# ledcontrol.net
KiCad netlist of a schematic drawn in EAGLE
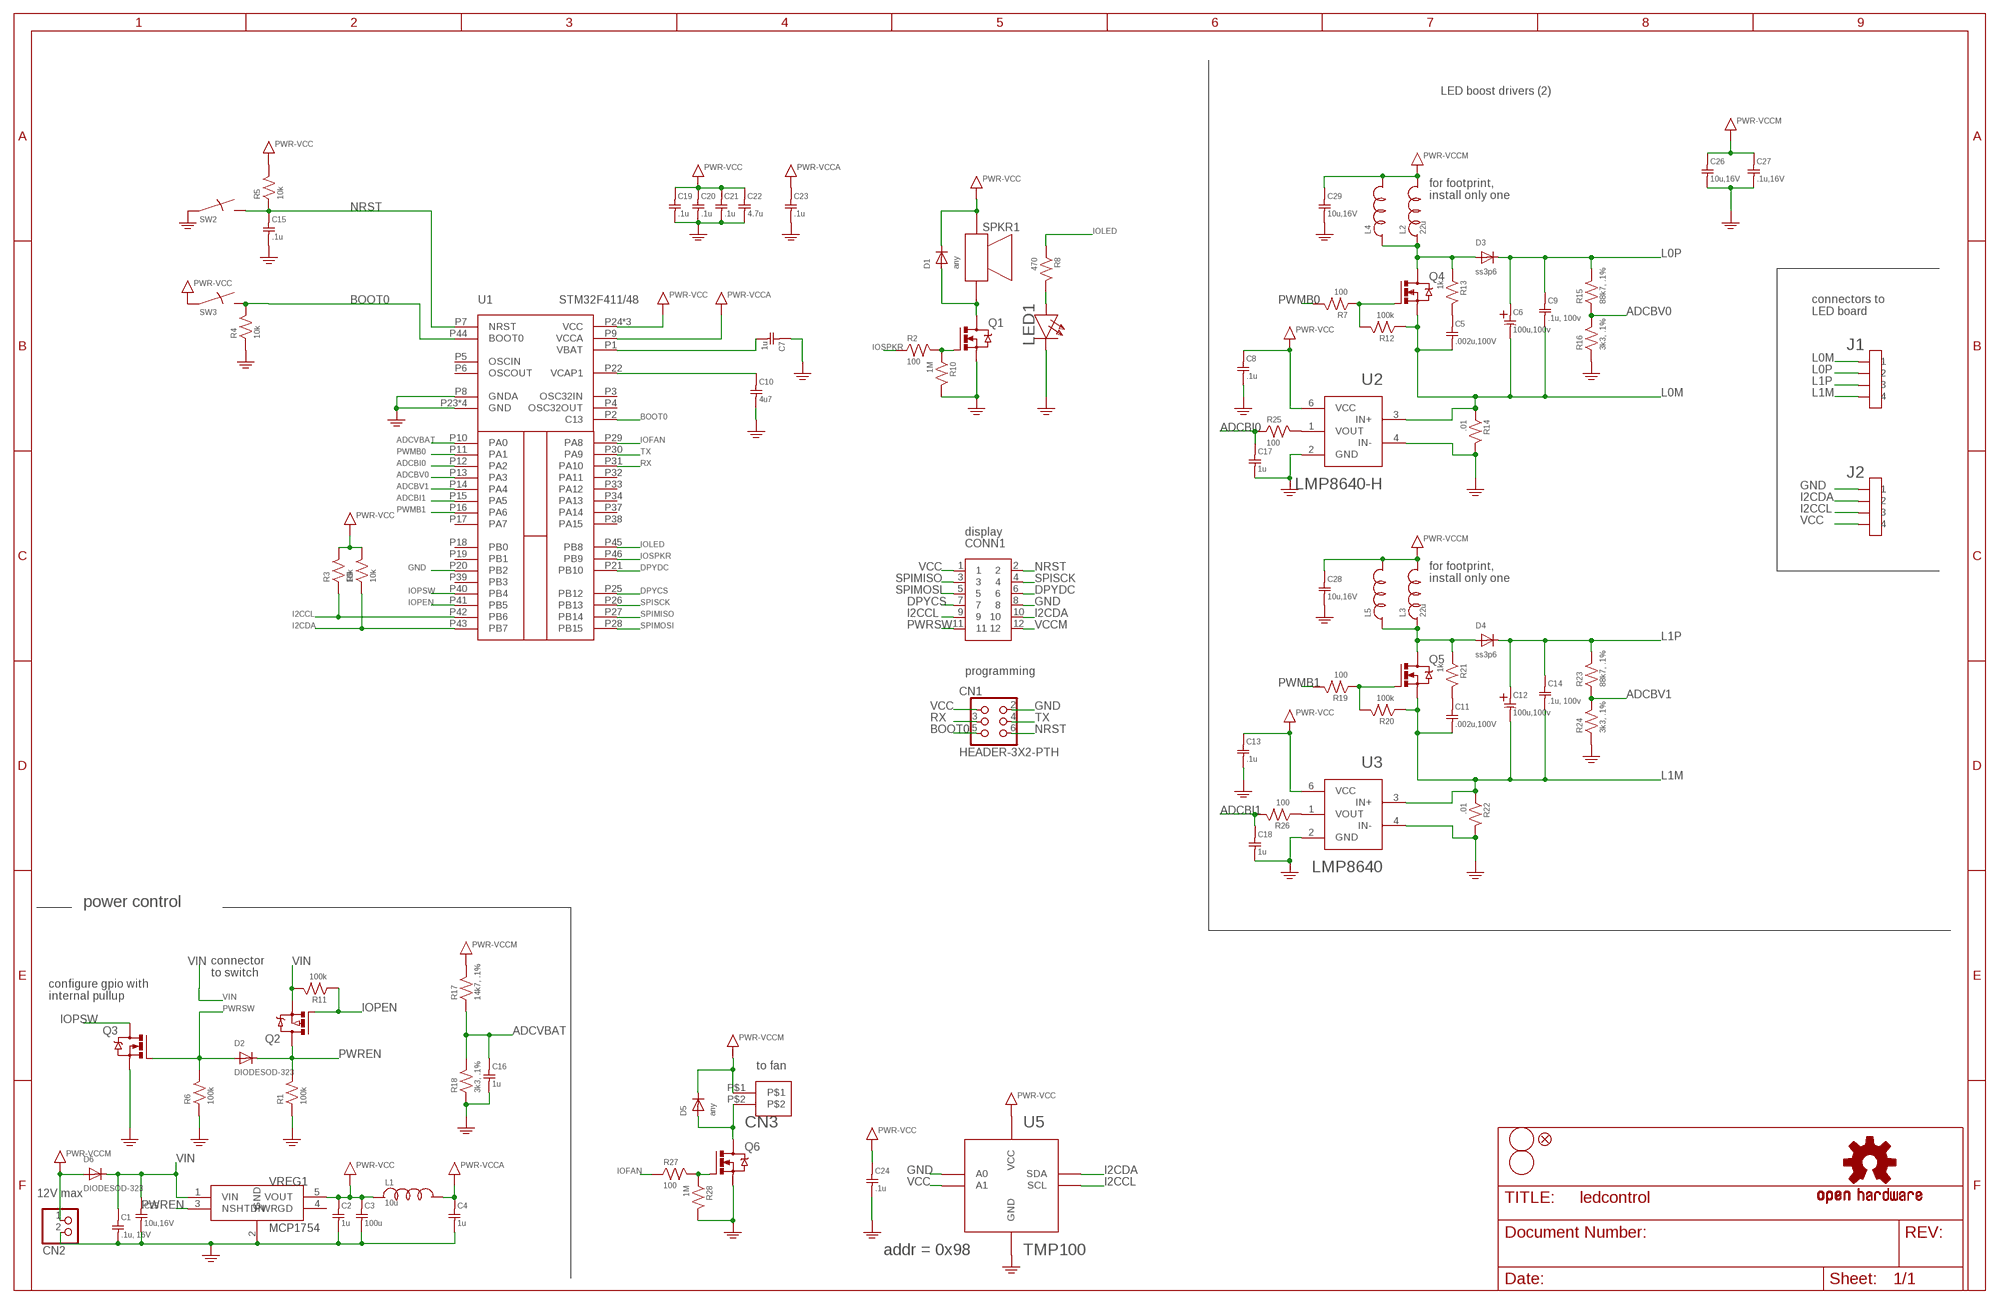
[diagram p0: schematic, sheet 1]

(export (version "E")
  (design (tool "Eeschema 10.0.6"))
  (components
    (comp (ref "C1")
      (value ".1u, 16V")
      (footprint "eagle-import:SMD0603")
      (libsource (lib "eagle-import") (part "C0603"))
    )
    (comp (ref "C2")
      (value "1u")
      (footprint "eagle-import:SMD0603")
      (libsource (lib "eagle-import") (part "C0603"))
    )
    (comp (ref "C3")
      (value "100u")
      (footprint "eagle-import:SMD1210")
      (libsource (lib "eagle-import") (part "C1210"))
    )
    (comp (ref "C4")
      (value "1u")
      (footprint "eagle-import:SMD0603")
      (libsource (lib "eagle-import") (part "C0603"))
    )
    (comp (ref "C5")
      (value ".002u,100V")
      (footprint "eagle-import:SMD0603")
      (libsource (lib "eagle-import") (part "C0603"))
    )
    (comp (ref "C6")
      (value "100u,100v")
      (footprint "eagle-import:CAPKE0")
      (libsource (lib "eagle-import") (part "C-POL-KE0"))
    )
    (comp (ref "C7")
      (value "1u")
      (footprint "eagle-import:SMD0603")
      (libsource (lib "eagle-import") (part "C0603"))
    )
    (comp (ref "C8")
      (value ".1u")
      (footprint "eagle-import:SMD0603")
      (libsource (lib "eagle-import") (part "C0603"))
    )
    (comp (ref "C9")
      (value ".1u, 100v")
      (footprint "eagle-import:SMD0805")
      (libsource (lib "eagle-import") (part "C0805"))
    )
    (comp (ref "C10")
      (value "4u7")
      (footprint "eagle-import:SMD0603")
      (libsource (lib "eagle-import") (part "C0603"))
    )
    (comp (ref "C11")
      (value ".002u,100V")
      (footprint "eagle-import:SMD0603")
      (libsource (lib "eagle-import") (part "C0603"))
    )
    (comp (ref "C12")
      (value "100u,100v")
      (footprint "eagle-import:CAPKE0")
      (libsource (lib "eagle-import") (part "C-POL-KE0"))
    )
    (comp (ref "C13")
      (value ".1u")
      (footprint "eagle-import:SMD0603")
      (libsource (lib "eagle-import") (part "C0603"))
    )
    (comp (ref "C14")
      (value ".1u, 100v")
      (footprint "eagle-import:SMD0805")
      (libsource (lib "eagle-import") (part "C0805"))
    )
    (comp (ref "C15")
      (value ".1u")
      (footprint "eagle-import:SMD0603")
      (libsource (lib "eagle-import") (part "C0603"))
    )
    (comp (ref "C16")
      (value "1u")
      (footprint "eagle-import:SMD0603")
      (libsource (lib "eagle-import") (part "C0603"))
    )
    (comp (ref "C17")
      (value "1u")
      (footprint "eagle-import:SMD0603")
      (libsource (lib "eagle-import") (part "C0603"))
    )
    (comp (ref "C18")
      (value "1u")
      (footprint "eagle-import:SMD0603")
      (libsource (lib "eagle-import") (part "C0603"))
    )
    (comp (ref "C19")
      (value ".1u")
      (footprint "eagle-import:SMD0603")
      (libsource (lib "eagle-import") (part "C0603"))
    )
    (comp (ref "C20")
      (value ".1u")
      (footprint "eagle-import:SMD0603")
      (libsource (lib "eagle-import") (part "C0603"))
    )
    (comp (ref "C21")
      (value ".1u")
      (footprint "eagle-import:SMD0603")
      (libsource (lib "eagle-import") (part "C0603"))
    )
    (comp (ref "C22")
      (value "4.7u")
      (footprint "eagle-import:SMD0603")
      (libsource (lib "eagle-import") (part "C0603"))
    )
    (comp (ref "C23")
      (value ".1u")
      (footprint "eagle-import:SMD0603")
      (libsource (lib "eagle-import") (part "C0603"))
    )
    (comp (ref "C24")
      (value ".1u")
      (footprint "eagle-import:SMD0603")
      (libsource (lib "eagle-import") (part "C0603"))
    )
    (comp (ref "C25")
      (value "10u,16V")
      (footprint "eagle-import:SMD0603")
      (libsource (lib "eagle-import") (part "C0603"))
    )
    (comp (ref "C26")
      (value "10u,16V")
      (footprint "eagle-import:SMD0603")
      (libsource (lib "eagle-import") (part "C0603"))
    )
    (comp (ref "C27")
      (value ".1u,16V")
      (footprint "eagle-import:SMD0603")
      (libsource (lib "eagle-import") (part "C0603"))
    )
    (comp (ref "C28")
      (value "10u,16V")
      (footprint "eagle-import:SMD0603")
      (libsource (lib "eagle-import") (part "C0603"))
    )
    (comp (ref "C29")
      (value "10u,16V")
      (footprint "eagle-import:SMD0603")
      (libsource (lib "eagle-import") (part "C0603"))
    )
    (comp (ref "CN1")
      (value "HEADER-3X2-PTH")
      (footprint "eagle-import:HEADER-3X2-PTH")
      (libsource (lib "eagle-import") (part "HEADER-3X2-PTH"))
    )
    (comp (ref "CN2")
      (value "JST_2PIN-THM-RA")
      (footprint "eagle-import:JST-PH-2-THM-RA")
      (libsource (lib "eagle-import") (part "JST_2PIN-THM-RA"))
    )
    (comp (ref "CN3")
      (value "HEADER-1X2-THM")
      (footprint "eagle-import:HEADER-1X2-THM")
      (libsource (lib "eagle-import") (part "HEADER-1X2-THM"))
    )
    (comp (ref "CONN1")
      (value "HEADER-6X2-PTH")
      (footprint "eagle-import:HEADER-6X2-PTH")
      (libsource (lib "eagle-import") (part "HEADER-6X2-PTH"))
    )
    (comp (ref "D1")
      (value "any")
      (footprint "eagle-import:SOD-323")
      (libsource (lib "eagle-import") (part "DIODESOD-323"))
    )
    (comp (ref "D2")
      (value "DIODESOD-323")
      (footprint "eagle-import:SOD-323")
      (libsource (lib "eagle-import") (part "DIODESOD-323"))
    )
    (comp (ref "D3")
      (value "ss3p6")
      (footprint "eagle-import:DO-214AC")
      (libsource (lib "eagle-import") (part "DIODEDO-214AC"))
    )
    (comp (ref "D4")
      (value "ss3p6")
      (footprint "eagle-import:DO-214AC")
      (libsource (lib "eagle-import") (part "DIODEDO-214AC"))
    )
    (comp (ref "D5")
      (value "any")
      (footprint "eagle-import:SOD-323")
      (libsource (lib "eagle-import") (part "DIODESOD-323"))
    )
    (comp (ref "D6")
      (value "DIODESOD-323")
      (footprint "eagle-import:SOD-323")
      (libsource (lib "eagle-import") (part "DIODESOD-323"))
    )
    (comp (ref "FID1")
      (value "FIDUCIALUFIDUCIAL")
      (footprint "eagle-import:MICRO-FIDUCIAL")
      (libsource (lib "eagle-import") (part "FIDUCIALUFIDUCIAL"))
    )
    (comp (ref "J1")
      (value "HEADER-4X1-PTH")
      (footprint "eagle-import:HEADER-4X1-PTH")
      (libsource (lib "eagle-import") (part "HEADER-4X1-PTH"))
    )
    (comp (ref "J2")
      (value "HEADER-4X1-PTH")
      (footprint "eagle-import:HEADER-4X1-PTH")
      (libsource (lib "eagle-import") (part "HEADER-4X1-PTH"))
    )
    (comp (ref "L1")
      (value "10u")
      (footprint "eagle-import:SMD0603")
      (libsource (lib "eagle-import") (part "LSMD0603"))
    )
    (comp (ref "L2")
      (value "22u")
      (footprint "eagle-import:BOURNS2303")
      (libsource (lib "eagle-import") (part "L2303"))
    )
    (comp (ref "L3")
      (value "22u")
      (footprint "eagle-import:BOURNS2303")
      (libsource (lib "eagle-import") (part "L2303"))
    )
    (comp (ref "L4")
      (value "L-SRR1260")
      (footprint "eagle-import:SRR1260")
      (libsource (lib "eagle-import") (part "L-SRR1260"))
    )
    (comp (ref "L5")
      (value "L-SRR1260")
      (footprint "eagle-import:SRR1260")
      (libsource (lib "eagle-import") (part "L-SRR1260"))
    )
    (comp (ref "LED1")
      (value "white")
      (footprint "eagle-import:SMD0603D")
      (libsource (lib "eagle-import") (part "LED"))
    )
    (comp (ref "LOGO1")
      (value "OSHW-LOGOS")
      (footprint "eagle-import:OSHW-LOGO-S")
      (libsource (lib "eagle-import") (part "OSHW-LOGOS"))
    )
    (comp (ref "Q1")
      (value "IRLML6344TRPBF")
      (footprint "eagle-import:SOT-23-3")
      (libsource (lib "eagle-import") (part "MOSFETSOT-23"))
    )
    (comp (ref "Q2")
      (value "MOSFET-P")
      (footprint "eagle-import:SOT-23-3@1")
      (libsource (lib "eagle-import") (part "MOSFET-P"))
    )
    (comp (ref "Q3")
      (value "MOSFETSOT-23")
      (footprint "eagle-import:SOT-23-3")
      (libsource (lib "eagle-import") (part "MOSFETSOT-23"))
    )
    (comp (ref "Q4")
      (value "AON6246")
      (footprint "eagle-import:DFN5X6-8LEP1")
      (libsource (lib "eagle-import") (part "MOSFET-DFN5X6"))
    )
    (comp (ref "Q5")
      (value "AON6246")
      (footprint "eagle-import:DFN5X6-8LEP1")
      (libsource (lib "eagle-import") (part "MOSFET-DFN5X6"))
    )
    (comp (ref "Q6")
      (value "IRLML6344TRPBF")
      (footprint "eagle-import:SOT-23-3")
      (libsource (lib "eagle-import") (part "MOSFETSOT-23"))
    )
    (comp (ref "R1")
      (value "100k")
      (footprint "eagle-import:SMD0603")
      (libsource (lib "eagle-import") (part "R0603"))
    )
    (comp (ref "R2")
      (value "100")
      (footprint "eagle-import:SMD0603")
      (libsource (lib "eagle-import") (part "R0603"))
    )
    (comp (ref "R3")
      (value "10k")
      (footprint "eagle-import:SMD0603")
      (libsource (lib "eagle-import") (part "R0603"))
    )
    (comp (ref "R4")
      (value "10k")
      (footprint "eagle-import:SMD0603")
      (libsource (lib "eagle-import") (part "R0603"))
    )
    (comp (ref "R5")
      (value "10k")
      (footprint "eagle-import:SMD0603")
      (libsource (lib "eagle-import") (part "R0603"))
    )
    (comp (ref "R6")
      (value "100k")
      (footprint "eagle-import:SMD0603")
      (libsource (lib "eagle-import") (part "R0603"))
    )
    (comp (ref "R7")
      (value "100")
      (footprint "eagle-import:SMD0603")
      (libsource (lib "eagle-import") (part "R0603"))
    )
    (comp (ref "R8")
      (value "470")
      (footprint "eagle-import:SMD0603")
      (libsource (lib "eagle-import") (part "R0603"))
    )
    (comp (ref "R9")
      (value "10k")
      (footprint "eagle-import:SMD0603")
      (libsource (lib "eagle-import") (part "R0603"))
    )
    (comp (ref "R10")
      (value "1M")
      (footprint "eagle-import:SMD0603")
      (libsource (lib "eagle-import") (part "R0603"))
    )
    (comp (ref "R11")
      (value "100k")
      (footprint "eagle-import:SMD0603")
      (libsource (lib "eagle-import") (part "R0603"))
    )
    (comp (ref "R12")
      (value "100k")
      (footprint "eagle-import:SMD0603")
      (libsource (lib "eagle-import") (part "R0603"))
    )
    (comp (ref "R13")
      (value "1k")
      (footprint "eagle-import:SMD0603")
      (libsource (lib "eagle-import") (part "R0603"))
    )
    (comp (ref "R14")
      (value ".01")
      (footprint "eagle-import:SMD1206")
      (libsource (lib "eagle-import") (part "R1206"))
    )
    (comp (ref "R15")
      (value "88k7, .1%")
      (footprint "eagle-import:SMD0603")
      (libsource (lib "eagle-import") (part "R0603"))
    )
    (comp (ref "R16")
      (value "3k3, .1%")
      (footprint "eagle-import:SMD0603")
      (libsource (lib "eagle-import") (part "R0603"))
    )
    (comp (ref "R17")
      (value "14k7, .1%")
      (footprint "eagle-import:SMD0603")
      (libsource (lib "eagle-import") (part "R0603"))
    )
    (comp (ref "R18")
      (value "3k3, .1%")
      (footprint "eagle-import:SMD0603")
      (libsource (lib "eagle-import") (part "R0603"))
    )
    (comp (ref "R19")
      (value "100")
      (footprint "eagle-import:SMD0603")
      (libsource (lib "eagle-import") (part "R0603"))
    )
    (comp (ref "R20")
      (value "100k")
      (footprint "eagle-import:SMD0603")
      (libsource (lib "eagle-import") (part "R0603"))
    )
    (comp (ref "R21")
      (value "1k")
      (footprint "eagle-import:SMD0603")
      (libsource (lib "eagle-import") (part "R0603"))
    )
    (comp (ref "R22")
      (value ".01")
      (footprint "eagle-import:SMD1206")
      (libsource (lib "eagle-import") (part "R1206"))
    )
    (comp (ref "R23")
      (value "88k7, .1%")
      (footprint "eagle-import:SMD0603")
      (libsource (lib "eagle-import") (part "R0603"))
    )
    (comp (ref "R24")
      (value "3k3, .1%")
      (footprint "eagle-import:SMD0603")
      (libsource (lib "eagle-import") (part "R0603"))
    )
    (comp (ref "R25")
      (value "100")
      (footprint "eagle-import:SMD0603")
      (libsource (lib "eagle-import") (part "R0603"))
    )
    (comp (ref "R26")
      (value "100")
      (footprint "eagle-import:SMD0603")
      (libsource (lib "eagle-import") (part "R0603"))
    )
    (comp (ref "R27")
      (value "100")
      (footprint "eagle-import:SMD0603")
      (libsource (lib "eagle-import") (part "R0603"))
    )
    (comp (ref "R28")
      (value "1M")
      (footprint "eagle-import:SMD0603")
      (libsource (lib "eagle-import") (part "R0603"))
    )
    (comp (ref "SPKR1")
      (value "PUI-5040")
      (footprint "eagle-import:PUI-0540")
      (libsource (lib "eagle-import") (part "PUI-5040"))
    )
    (comp (ref "SW2")
      (value "SWITCHKMR211")
      (footprint "eagle-import:KMR211")
      (libsource (lib "eagle-import") (part "SWITCHKMR211"))
    )
    (comp (ref "SW3")
      (value "SWITCHKMR211")
      (footprint "eagle-import:KMR211")
      (libsource (lib "eagle-import") (part "SWITCHKMR211"))
    )
    (comp (ref "U$1")
      (value "FIDUCIAL")
      (footprint "eagle-import:FIDUCIAL_1MM")
      (libsource (lib "eagle-import") (part "FIDUCIAL"))
    )
    (comp (ref "U$2")
      (value "FIDUCIAL")
      (footprint "eagle-import:FIDUCIAL_1MM")
      (libsource (lib "eagle-import") (part "FIDUCIAL"))
    )
    (comp (ref "U1")
      (value "STM32F411/48")
      (footprint "eagle-import:UQPFN48")
      (libsource (lib "eagle-import") (part "STM32F411/48"))
    )
    (comp (ref "U2")
      (value "LMP8640-H")
      (footprint "eagle-import:SOT-23-6")
      (libsource (lib "eagle-import") (part "LMP8640"))
    )
    (comp (ref "U3")
      (value "LMP8640")
      (footprint "eagle-import:SOT-23-6")
      (libsource (lib "eagle-import") (part "LMP8640"))
    )
    (comp (ref "U5")
      (value "TMP100")
      (footprint "eagle-import:SOT-23-6")
      (libsource (lib "eagle-import") (part "TMP100"))
    )
    (comp (ref "VREG1")
      (value "MCP1754")
      (footprint "eagle-import:SOT-23-5")
      (libsource (lib "eagle-import") (part "MCP1824"))
    )
  )
  (nets
    (net (code "1") (name "/ADCBI0") (class "Default")
      (node (ref "C17") (pin "1") (pinfunction "P$1_1") (pintype "passive"))
      (node (ref "R25") (pin "1") (pinfunction "P$1_1") (pintype "passive"))
      (node (ref "U1") (pin "P12") (pinfunction "PA2_P12") (pintype "bidirectional"))
    )
    (net (code "2") (name "/ADCBI1") (class "Default")
      (node (ref "C18") (pin "1") (pinfunction "P$1_1") (pintype "passive"))
      (node (ref "R26") (pin "2") (pinfunction "P$2_2") (pintype "passive"))
      (node (ref "U1") (pin "P15") (pinfunction "PA5_P15") (pintype "bidirectional"))
    )
    (net (code "3") (name "/ADCBV0") (class "Default")
      (node (ref "R15") (pin "1") (pinfunction "P$1_1") (pintype "passive"))
      (node (ref "R16") (pin "2") (pinfunction "P$2_2") (pintype "passive"))
      (node (ref "U1") (pin "P13") (pinfunction "PA3_P13") (pintype "bidirectional"))
    )
    (net (code "4") (name "/ADCBV1") (class "Default")
      (node (ref "R23") (pin "1") (pinfunction "P$1_1") (pintype "passive"))
      (node (ref "R24") (pin "2") (pinfunction "P$2_2") (pintype "passive"))
      (node (ref "U1") (pin "P14") (pinfunction "PA4_P14") (pintype "bidirectional"))
    )
    (net (code "5") (name "/ADCVBAT") (class "Default")
      (node (ref "C16") (pin "1") (pinfunction "P$1_1") (pintype "passive"))
      (node (ref "R17") (pin "1") (pinfunction "P$1_1") (pintype "passive"))
      (node (ref "R18") (pin "2") (pinfunction "P$2_2") (pintype "passive"))
      (node (ref "U1") (pin "P10") (pinfunction "PA0_P10") (pintype "bidirectional"))
    )
    (net (code "6") (name "/BOOT0") (class "Default")
      (node (ref "CN1") (pin "5") (pinfunction "P$5_5") (pintype "passive"))
      (node (ref "R4") (pin "2") (pinfunction "P$2_2") (pintype "passive"))
      (node (ref "SW3") (pin "2") (pinfunction "P$2_2") (pintype "passive"))
      (node (ref "SW3") (pin "4") (pinfunction "P$2_4") (pintype "passive"))
      (node (ref "U1") (pin "P2") (pinfunction "C13_P2") (pintype "bidirectional"))
      (node (ref "U1") (pin "P44") (pinfunction "BOOT0_P44") (pintype "bidirectional"))
    )
    (net (code "7") (name "/DPYCS") (class "Default")
      (node (ref "CONN1") (pin "7") (pinfunction "7_7") (pintype "bidirectional"))
      (node (ref "U1") (pin "P25") (pinfunction "PB12_P25") (pintype "bidirectional"))
    )
    (net (code "8") (name "/DPYDC") (class "Default")
      (node (ref "CONN1") (pin "6") (pinfunction "6_6") (pintype "bidirectional"))
      (node (ref "U1") (pin "P21") (pinfunction "PB10_P21") (pintype "bidirectional"))
    )
    (net (code "9") (name "/I2CCL") (class "Default")
      (node (ref "CONN1") (pin "9") (pinfunction "9_9") (pintype "bidirectional"))
      (node (ref "J2") (pin "P$3") (pinfunction "3_P$3") (pintype "bidirectional"))
      (node (ref "R3") (pin "1") (pinfunction "P$1_1") (pintype "passive"))
      (node (ref "U1") (pin "P42") (pinfunction "PB6_P42") (pintype "bidirectional"))
      (node (ref "U5") (pin "1") (pinfunction "SCL_1") (pintype "bidirectional"))
    )
    (net (code "10") (name "/I2CDA") (class "Default")
      (node (ref "CONN1") (pin "10") (pinfunction "10_10") (pintype "bidirectional"))
      (node (ref "J2") (pin "P$2") (pinfunction "2_P$2") (pintype "bidirectional"))
      (node (ref "R9") (pin "1") (pinfunction "P$1_1") (pintype "passive"))
      (node (ref "U1") (pin "P43") (pinfunction "PB7_P43") (pintype "bidirectional"))
      (node (ref "U5") (pin "6") (pinfunction "SDA_6") (pintype "bidirectional"))
    )
    (net (code "11") (name "/IOFAN") (class "Default")
      (node (ref "R27") (pin "1") (pinfunction "P$1_1") (pintype "passive"))
      (node (ref "U1") (pin "P29") (pinfunction "PA8_P29") (pintype "bidirectional"))
    )
    (net (code "12") (name "/IOLED") (class "Default")
      (node (ref "R8") (pin "1") (pinfunction "P$1_1") (pintype "passive"))
      (node (ref "U1") (pin "P45") (pinfunction "PB8_P45") (pintype "bidirectional"))
    )
    (net (code "13") (name "/IOPEN") (class "Default")
      (node (ref "Q2") (pin "1") (pinfunction "G_1") (pintype "passive"))
      (node (ref "R11") (pin "1") (pinfunction "P$1_1") (pintype "passive"))
      (node (ref "U1") (pin "P41") (pinfunction "PB5_P41") (pintype "bidirectional"))
    )
    (net (code "14") (name "/IOPSW") (class "Default")
      (node (ref "Q3") (pin "3") (pinfunction "D_3") (pintype "passive"))
      (node (ref "U1") (pin "P40") (pinfunction "PB4_P40") (pintype "bidirectional"))
    )
    (net (code "15") (name "/IOSPKR") (class "Default")
      (node (ref "R2") (pin "1") (pinfunction "P$1_1") (pintype "passive"))
      (node (ref "U1") (pin "P46") (pinfunction "PB9_P46") (pintype "bidirectional"))
    )
    (net (code "16") (name "/L0M") (class "Default")
      (node (ref "C5") (pin "2") (pinfunction "P$2_2") (pintype "passive"))
      (node (ref "C6") (pin "N") (pinfunction "P$2_N") (pintype "passive"))
      (node (ref "C9") (pin "2") (pinfunction "P$2_2") (pintype "passive"))
      (node (ref "J1") (pin "P$1") (pinfunction "1_P$1") (pintype "bidirectional"))
      (node (ref "Q4") (pin "P$1") (pinfunction "S_P$1") (pintype "passive"))
      (node (ref "Q4") (pin "P$2") (pinfunction "S_P$2") (pintype "passive"))
      (node (ref "Q4") (pin "P$3") (pinfunction "S_P$3") (pintype "passive"))
      (node (ref "R12") (pin "1") (pinfunction "P$1_1") (pintype "passive"))
      (node (ref "R14") (pin "1") (pinfunction "P$1_1") (pintype "passive"))
      (node (ref "U2") (pin "3") (pinfunction "IN+_3") (pintype "bidirectional"))
    )
    (net (code "17") (name "/L0P") (class "Default")
      (node (ref "C6") (pin "P") (pinfunction "P$1_P") (pintype "passive"))
      (node (ref "C9") (pin "1") (pinfunction "P$1_1") (pintype "passive"))
      (node (ref "D3") (pin "C") (pinfunction "C_C") (pintype "passive"))
      (node (ref "J1") (pin "P$2") (pinfunction "2_P$2") (pintype "bidirectional"))
      (node (ref "R15") (pin "2") (pinfunction "P$2_2") (pintype "passive"))
    )
    (net (code "18") (name "/L1M") (class "Default")
      (node (ref "C11") (pin "2") (pinfunction "P$2_2") (pintype "passive"))
      (node (ref "C12") (pin "N") (pinfunction "P$2_N") (pintype "passive"))
      (node (ref "C14") (pin "2") (pinfunction "P$2_2") (pintype "passive"))
      (node (ref "J1") (pin "P$4") (pinfunction "4_P$4") (pintype "bidirectional"))
      (node (ref "Q5") (pin "P$1") (pinfunction "S_P$1") (pintype "passive"))
      (node (ref "Q5") (pin "P$2") (pinfunction "S_P$2") (pintype "passive"))
      (node (ref "Q5") (pin "P$3") (pinfunction "S_P$3") (pintype "passive"))
      (node (ref "R20") (pin "1") (pinfunction "P$1_1") (pintype "passive"))
      (node (ref "R22") (pin "1") (pinfunction "P$1_1") (pintype "passive"))
      (node (ref "U3") (pin "3") (pinfunction "IN+_3") (pintype "bidirectional"))
    )
    (net (code "19") (name "/L1P") (class "Default")
      (node (ref "C12") (pin "P") (pinfunction "P$1_P") (pintype "passive"))
      (node (ref "C14") (pin "1") (pinfunction "P$1_1") (pintype "passive"))
      (node (ref "D4") (pin "C") (pinfunction "C_C") (pintype "passive"))
      (node (ref "J1") (pin "P$3") (pinfunction "3_P$3") (pintype "bidirectional"))
      (node (ref "R23") (pin "2") (pinfunction "P$2_2") (pintype "passive"))
    )
    (net (code "20") (name "/NRST") (class "Default")
      (node (ref "C15") (pin "1") (pinfunction "P$1_1") (pintype "passive"))
      (node (ref "CN1") (pin "6") (pinfunction "P$6_6") (pintype "passive"))
      (node (ref "CONN1") (pin "2") (pinfunction "2_2") (pintype "bidirectional"))
      (node (ref "R5") (pin "1") (pinfunction "P$1_1") (pintype "passive"))
      (node (ref "SW2") (pin "2") (pinfunction "P$2_2") (pintype "passive"))
      (node (ref "SW2") (pin "4") (pinfunction "P$2_4") (pintype "passive"))
      (node (ref "U1") (pin "P7") (pinfunction "NRST_P7") (pintype "bidirectional"))
    )
    (net (code "21") (name "/PWMB0") (class "Default")
      (node (ref "R7") (pin "2") (pinfunction "P$2_2") (pintype "passive"))
      (node (ref "U1") (pin "P11") (pinfunction "PA1_P11") (pintype "bidirectional"))
    )
    (net (code "22") (name "/PWMB1") (class "Default")
      (node (ref "R19") (pin "2") (pinfunction "P$2_2") (pintype "passive"))
      (node (ref "U1") (pin "P16") (pinfunction "PA6_P16") (pintype "bidirectional"))
    )
    (net (code "23") (name "/PWREN") (class "Default")
      (node (ref "D2") (pin "C") (pinfunction "C_C") (pintype "passive"))
      (node (ref "Q2") (pin "3") (pinfunction "D_3") (pintype "passive"))
      (node (ref "R1") (pin "2") (pinfunction "P$2_2") (pintype "passive"))
      (node (ref "VREG1") (pin "3") (pinfunction "NSHTDN_3") (pintype "bidirectional"))
    )
    (net (code "24") (name "/PWRSW") (class "Default")
      (node (ref "CONN1") (pin "11") (pinfunction "11_11") (pintype "bidirectional"))
      (node (ref "D2") (pin "A") (pinfunction "A_A") (pintype "passive"))
      (node (ref "Q3") (pin "1") (pinfunction "G_1") (pintype "passive"))
      (node (ref "R6") (pin "2") (pinfunction "P$2_2") (pintype "passive"))
    )
    (net (code "25") (name "/RX") (class "Default")
      (node (ref "CN1") (pin "3") (pinfunction "P$3_3") (pintype "passive"))
      (node (ref "U1") (pin "P31") (pinfunction "PA10_P31") (pintype "bidirectional"))
    )
    (net (code "26") (name "/SPIMISO") (class "Default")
      (node (ref "CONN1") (pin "3") (pinfunction "3_3") (pintype "bidirectional"))
      (node (ref "U1") (pin "P27") (pinfunction "PB14_P27") (pintype "bidirectional"))
    )
    (net (code "27") (name "/SPIMOSI") (class "Default")
      (node (ref "CONN1") (pin "5") (pinfunction "5_5") (pintype "bidirectional"))
      (node (ref "U1") (pin "P28") (pinfunction "PB15_P28") (pintype "bidirectional"))
    )
    (net (code "28") (name "/SPISCK") (class "Default")
      (node (ref "CONN1") (pin "4") (pinfunction "4_4") (pintype "bidirectional"))
      (node (ref "U1") (pin "P26") (pinfunction "PB13_P26") (pintype "bidirectional"))
    )
    (net (code "29") (name "/TX") (class "Default")
      (node (ref "CN1") (pin "4") (pinfunction "P$4_4") (pintype "passive"))
      (node (ref "U1") (pin "P30") (pinfunction "PA9_P30") (pintype "bidirectional"))
    )
    (net (code "30") (name "/VIN") (class "Default")
      (node (ref "C1") (pin "1") (pinfunction "P$1_1") (pintype "passive"))
      (node (ref "C25") (pin "1") (pinfunction "P$1_1") (pintype "passive"))
      (node (ref "D6") (pin "C") (pinfunction "C_C") (pintype "passive"))
      (node (ref "Q2") (pin "2") (pinfunction "S_2") (pintype "passive"))
      (node (ref "R11") (pin "2") (pinfunction "P$2_2") (pintype "passive"))
      (node (ref "VREG1") (pin "1") (pinfunction "VIN_1") (pintype "bidirectional"))
    )
    (net (code "31") (name "Net-(C5-P$1)") (class "Default")
      (node (ref "C5") (pin "1") (pinfunction "P$1_1") (pintype "passive"))
      (node (ref "R13") (pin "2") (pinfunction "P$2_2") (pintype "passive"))
    )
    (net (code "32") (name "Net-(C7-P$2)") (class "Default")
      (node (ref "C7") (pin "2") (pinfunction "P$2_2") (pintype "passive"))
      (node (ref "U1") (pin "P1") (pinfunction "VBAT_P1") (pintype "bidirectional"))
    )
    (net (code "33") (name "Net-(C10-P$1)") (class "Default")
      (node (ref "C10") (pin "1") (pinfunction "P$1_1") (pintype "passive"))
      (node (ref "U1") (pin "P22") (pinfunction "VCAP1_P22") (pintype "bidirectional"))
    )
    (net (code "34") (name "Net-(C11-P$1)") (class "Default")
      (node (ref "C11") (pin "1") (pinfunction "P$1_1") (pintype "passive"))
      (node (ref "R21") (pin "2") (pinfunction "P$2_2") (pintype "passive"))
    )
    (net (code "35") (name "Net-(Q1-D)") (class "Default")
      (node (ref "D1") (pin "A") (pinfunction "A_A") (pintype "passive"))
      (node (ref "Q1") (pin "3") (pinfunction "D_3") (pintype "passive"))
      (node (ref "SPKR1") (pin "P2") (pinfunction "P2_P2") (pintype "input"))
    )
    (net (code "36") (name "Net-(Q1-G)") (class "Default")
      (node (ref "Q1") (pin "1") (pinfunction "G_1") (pintype "passive"))
      (node (ref "R10") (pin "1") (pinfunction "P$1_1") (pintype "passive"))
      (node (ref "R2") (pin "2") (pinfunction "P$2_2") (pintype "passive"))
    )
    (net (code "37") (name "Net-(Q4-G)") (class "Default")
      (node (ref "Q4") (pin "P$4") (pinfunction "G_P$4") (pintype "passive"))
      (node (ref "R12") (pin "2") (pinfunction "P$2_2") (pintype "passive"))
      (node (ref "R7") (pin "1") (pinfunction "P$1_1") (pintype "passive"))
    )
    (net (code "38") (name "Net-(Q5-G)") (class "Default")
      (node (ref "Q5") (pin "P$4") (pinfunction "G_P$4") (pintype "passive"))
      (node (ref "R19") (pin "1") (pinfunction "P$1_1") (pintype "passive"))
      (node (ref "R20") (pin "2") (pinfunction "P$2_2") (pintype "passive"))
    )
    (net (code "39") (name "Net-(Q6-D)") (class "Default")
      (node (ref "CN3") (pin "P$2") (pinfunction "P$2_P$2") (pintype "bidirectional"))
      (node (ref "D5") (pin "A") (pinfunction "A_A") (pintype "passive"))
      (node (ref "Q6") (pin "3") (pinfunction "D_3") (pintype "passive"))
    )
    (net (code "40") (name "Net-(Q6-G)") (class "Default")
      (node (ref "Q6") (pin "1") (pinfunction "G_1") (pintype "passive"))
      (node (ref "R27") (pin "2") (pinfunction "P$2_2") (pintype "passive"))
      (node (ref "R28") (pin "1") (pinfunction "P$1_1") (pintype "passive"))
    )
    (net (code "41") (name "Net-(R8-P$2)") (class "Default")
      (node (ref "LED1") (pin "A") (pinfunction "A_A") (pintype "passive"))
      (node (ref "R8") (pin "2") (pinfunction "P$2_2") (pintype "passive"))
    )
    (net (code "42") (name "Net-(R13-P$1)") (class "Default")
      (node (ref "D3") (pin "A") (pinfunction "A_A") (pintype "passive"))
      (node (ref "L2") (pin "P$1") (pinfunction "P$1_P$1") (pintype "passive"))
      (node (ref "L4") (pin "P$1") (pinfunction "P$1_P$1") (pintype "passive"))
      (node (ref "Q4") (pin "P$5") (pinfunction "D_P$5") (pintype "passive"))
      (node (ref "Q4") (pin "P$6") (pinfunction "D_P$6") (pintype "passive"))
      (node (ref "Q4") (pin "P$7") (pinfunction "D_P$7") (pintype "passive"))
      (node (ref "Q4") (pin "P$8") (pinfunction "D_P$8") (pintype "passive"))
      (node (ref "Q4") (pin "P$9") (pinfunction "D_P$9") (pintype "passive"))
      (node (ref "R13") (pin "1") (pinfunction "P$1_1") (pintype "passive"))
    )
    (net (code "43") (name "Net-(R21-P$1)") (class "Default")
      (node (ref "D4") (pin "A") (pinfunction "A_A") (pintype "passive"))
      (node (ref "L3") (pin "P$1") (pinfunction "P$1_P$1") (pintype "passive"))
      (node (ref "L5") (pin "P$1") (pinfunction "P$1_P$1") (pintype "passive"))
      (node (ref "Q5") (pin "P$5") (pinfunction "D_P$5") (pintype "passive"))
      (node (ref "Q5") (pin "P$6") (pinfunction "D_P$6") (pintype "passive"))
      (node (ref "Q5") (pin "P$7") (pinfunction "D_P$7") (pintype "passive"))
      (node (ref "Q5") (pin "P$8") (pinfunction "D_P$8") (pintype "passive"))
      (node (ref "Q5") (pin "P$9") (pinfunction "D_P$9") (pintype "passive"))
      (node (ref "R21") (pin "1") (pinfunction "P$1_1") (pintype "passive"))
    )
    (net (code "44") (name "Net-(R25-P$2)") (class "Default")
      (node (ref "R25") (pin "2") (pinfunction "P$2_2") (pintype "passive"))
      (node (ref "U2") (pin "1") (pinfunction "VOUT_1") (pintype "bidirectional"))
    )
    (net (code "45") (name "Net-(R26-P$1)") (class "Default")
      (node (ref "R26") (pin "1") (pinfunction "P$1_1") (pintype "passive"))
      (node (ref "U3") (pin "1") (pinfunction "VOUT_1") (pintype "bidirectional"))
    )
    (net (code "46") (name "PWR-GND") (class "Default")
      (node (ref "C1") (pin "2") (pinfunction "P$2_2") (pintype "passive"))
      (node (ref "C10") (pin "2") (pinfunction "P$2_2") (pintype "passive"))
      (node (ref "C13") (pin "2") (pinfunction "P$2_2") (pintype "passive"))
      (node (ref "C15") (pin "2") (pinfunction "P$2_2") (pintype "passive"))
      (node (ref "C16") (pin "2") (pinfunction "P$2_2") (pintype "passive"))
      (node (ref "C17") (pin "2") (pinfunction "P$2_2") (pintype "passive"))
      (node (ref "C18") (pin "2") (pinfunction "P$2_2") (pintype "passive"))
      (node (ref "C19") (pin "2") (pinfunction "P$2_2") (pintype "passive"))
      (node (ref "C2") (pin "2") (pinfunction "P$2_2") (pintype "passive"))
      (node (ref "C20") (pin "2") (pinfunction "P$2_2") (pintype "passive"))
      (node (ref "C21") (pin "2") (pinfunction "P$2_2") (pintype "passive"))
      (node (ref "C22") (pin "2") (pinfunction "P$2_2") (pintype "passive"))
      (node (ref "C23") (pin "2") (pinfunction "P$2_2") (pintype "passive"))
      (node (ref "C24") (pin "2") (pinfunction "P$2_2") (pintype "passive"))
      (node (ref "C25") (pin "2") (pinfunction "P$2_2") (pintype "passive"))
      (node (ref "C26") (pin "2") (pinfunction "P$2_2") (pintype "passive"))
      (node (ref "C27") (pin "2") (pinfunction "P$2_2") (pintype "passive"))
      (node (ref "C28") (pin "2") (pinfunction "P$2_2") (pintype "passive"))
      (node (ref "C29") (pin "2") (pinfunction "P$2_2") (pintype "passive"))
      (node (ref "C3") (pin "2") (pinfunction "P$2_2") (pintype "passive"))
      (node (ref "C4") (pin "2") (pinfunction "P$2_2") (pintype "passive"))
      (node (ref "C7") (pin "1") (pinfunction "P$1_1") (pintype "passive"))
      (node (ref "C8") (pin "2") (pinfunction "P$2_2") (pintype "passive"))
      (node (ref "CN1") (pin "2") (pinfunction "P$2_2") (pintype "passive"))
      (node (ref "CN2") (pin "2") (pinfunction "1_2") (pintype "passive"))
      (node (ref "CONN1") (pin "8") (pinfunction "8_8") (pintype "bidirectional"))
      (node (ref "J2") (pin "P$1") (pinfunction "1_P$1") (pintype "bidirectional"))
      (node (ref "LED1") (pin "C") (pinfunction "C_C") (pintype "passive"))
      (node (ref "Q1") (pin "2") (pinfunction "S_2") (pintype "passive"))
      (node (ref "Q3") (pin "2") (pinfunction "S_2") (pintype "passive"))
      (node (ref "Q6") (pin "2") (pinfunction "S_2") (pintype "passive"))
      (node (ref "R1") (pin "1") (pinfunction "P$1_1") (pintype "passive"))
      (node (ref "R10") (pin "2") (pinfunction "P$2_2") (pintype "passive"))
      (node (ref "R14") (pin "2") (pinfunction "P$2_2") (pintype "passive"))
      (node (ref "R16") (pin "1") (pinfunction "P$1_1") (pintype "passive"))
      (node (ref "R18") (pin "1") (pinfunction "P$1_1") (pintype "passive"))
      (node (ref "R22") (pin "2") (pinfunction "P$2_2") (pintype "passive"))
      (node (ref "R24") (pin "1") (pinfunction "P$1_1") (pintype "passive"))
      (node (ref "R28") (pin "2") (pinfunction "P$2_2") (pintype "passive"))
      (node (ref "R4") (pin "1") (pinfunction "P$1_1") (pintype "passive"))
      (node (ref "R6") (pin "1") (pinfunction "P$1_1") (pintype "passive"))
      (node (ref "SW2") (pin "1") (pinfunction "P$1_1") (pintype "passive"))
      (node (ref "SW2") (pin "3") (pinfunction "P$1_3") (pintype "passive"))
      (node (ref "U1") (pin "P20") (pinfunction "PB2_P20") (pintype "bidirectional"))
      (node (ref "U1") (pin "P23") (pinfunction "GND_P23") (pintype "bidirectional"))
      (node (ref "U1") (pin "P35") (pinfunction "GND_P35") (pintype "bidirectional"))
      (node (ref "U1") (pin "P47") (pinfunction "GND_P47") (pintype "bidirectional"))
      (node (ref "U1") (pin "P8") (pinfunction "GNDA_P8") (pintype "bidirectional"))
      (node (ref "U1") (pin "PAD") (pinfunction "GND_PAD") (pintype "bidirectional"))
      (node (ref "U2") (pin "2") (pinfunction "GND_2") (pintype "bidirectional"))
      (node (ref "U2") (pin "4") (pinfunction "IN-_4") (pintype "bidirectional"))
      (node (ref "U3") (pin "2") (pinfunction "GND_2") (pintype "bidirectional"))
      (node (ref "U3") (pin "4") (pinfunction "IN-_4") (pintype "bidirectional"))
      (node (ref "U5") (pin "2") (pinfunction "GND_2") (pintype "bidirectional"))
      (node (ref "U5") (pin "5") (pinfunction "A0_5") (pintype "bidirectional"))
      (node (ref "VREG1") (pin "2") (pinfunction "GND_2") (pintype "bidirectional"))
    )
    (net (code "47") (name "PWR-VCC") (class "Default")
      (node (ref "C13") (pin "1") (pinfunction "P$1_1") (pintype "passive"))
      (node (ref "C19") (pin "1") (pinfunction "P$1_1") (pintype "passive"))
      (node (ref "C2") (pin "1") (pinfunction "P$1_1") (pintype "passive"))
      (node (ref "C20") (pin "1") (pinfunction "P$1_1") (pintype "passive"))
      (node (ref "C21") (pin "1") (pinfunction "P$1_1") (pintype "passive"))
      (node (ref "C22") (pin "1") (pinfunction "P$1_1") (pintype "passive"))
      (node (ref "C24") (pin "1") (pinfunction "P$1_1") (pintype "passive"))
      (node (ref "C3") (pin "1") (pinfunction "P$1_1") (pintype "passive"))
      (node (ref "C8") (pin "1") (pinfunction "P$1_1") (pintype "passive"))
      (node (ref "CN1") (pin "1") (pinfunction "P$1_1") (pintype "passive"))
      (node (ref "CONN1") (pin "1") (pinfunction "1_1") (pintype "bidirectional"))
      (node (ref "D1") (pin "C") (pinfunction "C_C") (pintype "passive"))
      (node (ref "J2") (pin "P$4") (pinfunction "4_P$4") (pintype "bidirectional"))
      (node (ref "L1") (pin "1") (pinfunction "P$1_1") (pintype "passive"))
      (node (ref "R3") (pin "2") (pinfunction "P$2_2") (pintype "passive"))
      (node (ref "R5") (pin "2") (pinfunction "P$2_2") (pintype "passive"))
      (node (ref "R9") (pin "2") (pinfunction "P$2_2") (pintype "passive"))
      (node (ref "SPKR1") (pin "P1") (pinfunction "P1_P1") (pintype "input"))
      (node (ref "SW3") (pin "1") (pinfunction "P$1_1") (pintype "passive"))
      (node (ref "SW3") (pin "3") (pinfunction "P$1_3") (pintype "passive"))
      (node (ref "U1") (pin "P24") (pinfunction "VCC_P24") (pintype "bidirectional"))
      (node (ref "U1") (pin "P36") (pinfunction "VCC_P36") (pintype "bidirectional"))
      (node (ref "U1") (pin "P48") (pinfunction "VCC_P48") (pintype "bidirectional"))
      (node (ref "U2") (pin "6") (pinfunction "VCC_6") (pintype "bidirectional"))
      (node (ref "U3") (pin "6") (pinfunction "VCC_6") (pintype "bidirectional"))
      (node (ref "U5") (pin "3") (pinfunction "A1_3") (pintype "bidirectional"))
      (node (ref "U5") (pin "4") (pinfunction "VCC_4") (pintype "bidirectional"))
      (node (ref "VREG1") (pin "5") (pinfunction "VOUT_5") (pintype "bidirectional"))
    )
    (net (code "48") (name "PWR-VCCA") (class "Default")
      (node (ref "C23") (pin "1") (pinfunction "P$1_1") (pintype "passive"))
      (node (ref "C4") (pin "1") (pinfunction "P$1_1") (pintype "passive"))
      (node (ref "L1") (pin "2") (pinfunction "P$2_2") (pintype "passive"))
      (node (ref "U1") (pin "P9") (pinfunction "VCCA_P9") (pintype "bidirectional"))
    )
    (net (code "49") (name "PWR-VCCM") (class "Default")
      (node (ref "C26") (pin "1") (pinfunction "P$1_1") (pintype "passive"))
      (node (ref "C27") (pin "1") (pinfunction "P$1_1") (pintype "passive"))
      (node (ref "C28") (pin "1") (pinfunction "P$1_1") (pintype "passive"))
      (node (ref "C29") (pin "1") (pinfunction "P$1_1") (pintype "passive"))
      (node (ref "CN2") (pin "1") (pinfunction "2_1") (pintype "passive"))
      (node (ref "CN3") (pin "P$1") (pinfunction "P$1_P$1") (pintype "bidirectional"))
      (node (ref "CONN1") (pin "12") (pinfunction "12_12") (pintype "bidirectional"))
      (node (ref "D5") (pin "C") (pinfunction "C_C") (pintype "passive"))
      (node (ref "D6") (pin "A") (pinfunction "A_A") (pintype "passive"))
      (node (ref "L2") (pin "P$2") (pinfunction "P$2_P$2") (pintype "passive"))
      (node (ref "L3") (pin "P$2") (pinfunction "P$2_P$2") (pintype "passive"))
      (node (ref "L4") (pin "P$2") (pinfunction "P$2_P$2") (pintype "passive"))
      (node (ref "L5") (pin "P$2") (pinfunction "P$2_P$2") (pintype "passive"))
      (node (ref "R17") (pin "2") (pinfunction "P$2_2") (pintype "passive"))
    )
    (net (code "50") (name "unconnected-(U1-OSC32IN-PadP3)") (class "Default")
      (node (ref "U1") (pin "P3") (pinfunction "OSC32IN_P3") (pintype "bidirectional"))
    )
    (net (code "51") (name "unconnected-(U1-OSC32OUT-PadP4)") (class "Default")
      (node (ref "U1") (pin "P4") (pinfunction "OSC32OUT_P4") (pintype "bidirectional"))
    )
    (net (code "52") (name "unconnected-(U1-OSCIN-PadP5)") (class "Default")
      (node (ref "U1") (pin "P5") (pinfunction "OSCIN_P5") (pintype "bidirectional"))
    )
    (net (code "53") (name "unconnected-(U1-OSCOUT-PadP6)") (class "Default")
      (node (ref "U1") (pin "P6") (pinfunction "OSCOUT_P6") (pintype "bidirectional"))
    )
    (net (code "54") (name "unconnected-(U1-PA7-PadP17)") (class "Default")
      (node (ref "U1") (pin "P17") (pinfunction "PA7_P17") (pintype "bidirectional"))
    )
    (net (code "55") (name "unconnected-(U1-PA11-PadP32)") (class "Default")
      (node (ref "U1") (pin "P32") (pinfunction "PA11_P32") (pintype "bidirectional"))
    )
    (net (code "56") (name "unconnected-(U1-PA12-PadP33)") (class "Default")
      (node (ref "U1") (pin "P33") (pinfunction "PA12_P33") (pintype "bidirectional"))
    )
    (net (code "57") (name "unconnected-(U1-PA13-PadP34)") (class "Default")
      (node (ref "U1") (pin "P34") (pinfunction "PA13_P34") (pintype "bidirectional"))
    )
    (net (code "58") (name "unconnected-(U1-PA14-PadP37)") (class "Default")
      (node (ref "U1") (pin "P37") (pinfunction "PA14_P37") (pintype "bidirectional"))
    )
    (net (code "59") (name "unconnected-(U1-PA15-PadP38)") (class "Default")
      (node (ref "U1") (pin "P38") (pinfunction "PA15_P38") (pintype "bidirectional"))
    )
    (net (code "60") (name "unconnected-(U1-PB0-PadP18)") (class "Default")
      (node (ref "U1") (pin "P18") (pinfunction "PB0_P18") (pintype "bidirectional"))
    )
    (net (code "61") (name "unconnected-(U1-PB1-PadP19)") (class "Default")
      (node (ref "U1") (pin "P19") (pinfunction "PB1_P19") (pintype "bidirectional"))
    )
    (net (code "62") (name "unconnected-(U1-PB3-PadP39)") (class "Default")
      (node (ref "U1") (pin "P39") (pinfunction "PB3_P39") (pintype "bidirectional"))
    )
    (net (code "63") (name "unconnected-(VREG1-PWRGD-Pad4)") (class "Default")
      (node (ref "VREG1") (pin "4") (pinfunction "PWRGD_4") (pintype "bidirectional"))
    )
  )
)
